# Sheet1.net
KiCad netlist of a schematic drawn in Altium Designer
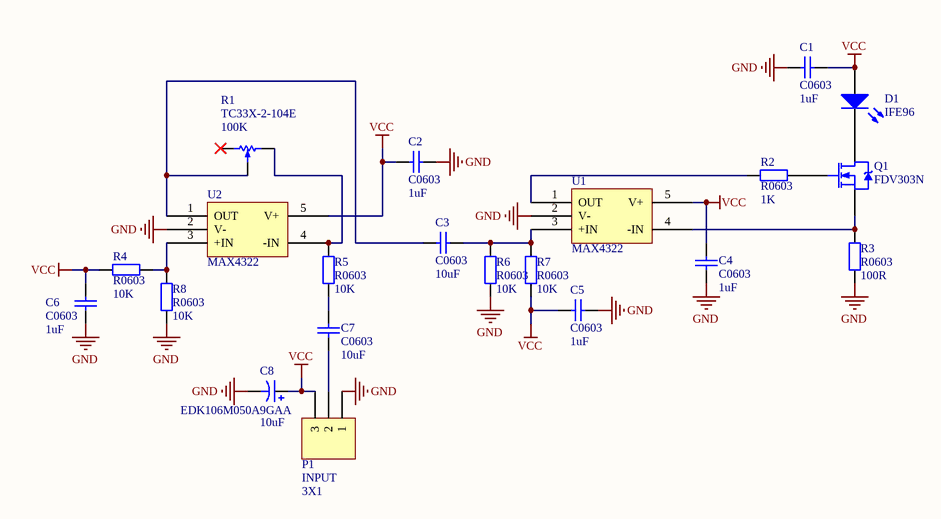
[diagram p0: Sheet1.SchDoc]

(export (version "E")
  (design (tool "Eeschema 10.0.6"))
  (components
    (comp (ref "C1")
      (value "C0603")
      (footprint "1608[0603]")
      (description "Ceramic Capacitor")
      (fields (field (name "ALTIUM_VALUE") "1uF"))
      (libsource (lib "Miscellaneous Devices Local Copy") (part "Cap"))
    )
    (comp (ref "C2")
      (value "C0603")
      (footprint "1608[0603]")
      (description "Ceramic Capacitor")
      (fields (field (name "ALTIUM_VALUE") "1uF"))
      (libsource (lib "Miscellaneous Devices Local Copy") (part "Cap"))
    )
    (comp (ref "C3")
      (value "C0603")
      (footprint "1608[0603]")
      (description "Ceramic Capacitor")
      (fields (field (name "ALTIUM_VALUE") "10uF"))
      (libsource (lib "Miscellaneous Devices Local Copy") (part "Cap"))
    )
    (comp (ref "C4")
      (value "C0603")
      (footprint "1608[0603]")
      (description "Ceramic Capacitor")
      (fields (field (name "ALTIUM_VALUE") "1uF"))
      (libsource (lib "Miscellaneous Devices Local Copy") (part "Cap"))
    )
    (comp (ref "C5")
      (value "C0603")
      (footprint "1608[0603]")
      (description "Ceramic Capacitor")
      (fields (field (name "ALTIUM_VALUE") "1uF"))
      (libsource (lib "Miscellaneous Devices Local Copy") (part "Cap"))
    )
    (comp (ref "C6")
      (value "C0603")
      (footprint "1608[0603]")
      (description "Ceramic Capacitor")
      (fields (field (name "ALTIUM_VALUE") "1uF"))
      (libsource (lib "Miscellaneous Devices Local Copy") (part "Cap"))
    )
    (comp (ref "C7")
      (value "C0603")
      (footprint "1608[0603]")
      (description "Ceramic Capacitor")
      (fields (field (name "ALTIUM_VALUE") "10uF"))
      (libsource (lib "Miscellaneous Devices Local Copy") (part "Cap"))
    )
    (comp (ref "C8")
      (value "EDK106M050A9GAA")
      (footprint "EDK106M050A9GAA")
      (description "Aluminium Electrolytic Capacitor")
      (fields (field (name "ALTIUM_VALUE") "10uF"))
      (libsource (lib "Miscellaneous Devices Local Copy") (part "Cap Pol1"))
    )
    (comp (ref "D1")
      (value "IFE96")
      (footprint "IFE96")
      (description "Red LED For PMMA")
      (libsource (lib "Schlib1") (part "IFE96"))
    )
    (comp (ref "P1")
      (value "INPUT")
      (footprint "HDR1X3")
      (description "Header, 3-Pin")
      (fields (field (name "ALTIUM_VALUE") "3X1"))
      (libsource (lib "Miscellaneous Connectors Local Copy") (part "Header 3"))
    )
    (comp (ref "Q1")
      (value "FDV303N")
      (footprint "SOT23_M")
      (description "N-channel MOS FET Transistor")
      (libsource (lib "Schlib1") (part "FDV303N"))
    )
    (comp (ref "R1")
      (value "TC33X-2-104E")
      (footprint "TC33X-2-104E")
      (description "Potentiometer")
      (fields (field (name "ALTIUM_VALUE") "100K"))
      (libsource (lib "Schlib1") (part "TC33X-2-104E"))
    )
    (comp (ref "R2")
      (value "R0603")
      (footprint "J1-0603")
      (description "Resistor")
      (fields (field (name "ALTIUM_VALUE") "1K"))
      (libsource (lib "Miscellaneous Devices Local Copy") (part "Res2"))
    )
    (comp (ref "R3")
      (value "R0603")
      (footprint "J1-0603")
      (description "Resistor")
      (fields (field (name "ALTIUM_VALUE") "100R"))
      (libsource (lib "") (part "Res2_1"))
    )
    (comp (ref "R4")
      (value "R0603")
      (footprint "J1-0603")
      (description "Resistor")
      (fields (field (name "ALTIUM_VALUE") "10K"))
      (libsource (lib "Miscellaneous Devices Local Copy") (part "Res2"))
    )
    (comp (ref "R5")
      (value "R0603")
      (footprint "J1-0603")
      (description "Resistor")
      (fields (field (name "ALTIUM_VALUE") "10K"))
      (libsource (lib "") (part "Res2_1"))
    )
    (comp (ref "R6")
      (value "R0603")
      (footprint "J1-0603")
      (description "Resistor")
      (fields (field (name "ALTIUM_VALUE") "10K"))
      (libsource (lib "") (part "Res2_1"))
    )
    (comp (ref "R7")
      (value "R0603")
      (footprint "J1-0603")
      (description "Resistor")
      (fields (field (name "ALTIUM_VALUE") "10K"))
      (libsource (lib "") (part "Res2_1"))
    )
    (comp (ref "R8")
      (value "R0603")
      (footprint "J1-0603")
      (description "Resistor")
      (fields (field (name "ALTIUM_VALUE") "10K"))
      (libsource (lib "") (part "Res2_2"))
    )
    (comp (ref "U1")
      (value "MAX4322")
      (footprint "MAX4322_SOT23-5")
      (description "Single Supply Operational Amplifier")
      (libsource (lib "Schlib1") (part "MAX4322"))
    )
    (comp (ref "U2")
      (value "MAX4322")
      (footprint "MAX4322_SOT23-5")
      (description "Single Supply Operational Amplifier")
      (libsource (lib "Schlib1") (part "MAX4322"))
    )
  )
  (nets
    (net (code "1") (name "GND") (class "Default")
      (node (ref "C1") (pin "2") (pinfunction "2_2") (pintype "passive"))
      (node (ref "C2") (pin "2") (pinfunction "2_2") (pintype "passive"))
      (node (ref "C4") (pin "1") (pinfunction "1_1") (pintype "passive"))
      (node (ref "C5") (pin "2") (pinfunction "2_2") (pintype "passive"))
      (node (ref "C6") (pin "1") (pinfunction "1_1") (pintype "passive"))
      (node (ref "C8") (pin "2") (pinfunction "2_2") (pintype "passive"))
      (node (ref "P1") (pin "1") (pinfunction "1_1") (pintype "passive"))
      (node (ref "R3") (pin "2") (pinfunction "2_2") (pintype "passive"))
      (node (ref "R6") (pin "2") (pinfunction "2_2") (pintype "passive"))
      (node (ref "R8") (pin "1") (pinfunction "1_1") (pintype "passive"))
      (node (ref "U1") (pin "2") (pinfunction "V-_2") (pintype "passive"))
      (node (ref "U2") (pin "2") (pinfunction "V-_2") (pintype "passive"))
    )
    (net (code "2") (name "Net-(C7-Pad1)") (class "Default")
      (node (ref "C7") (pin "1") (pinfunction "1_1") (pintype "passive"))
      (node (ref "P1") (pin "2") (pinfunction "2_2") (pintype "passive"))
    )
    (net (code "3") (name "Net-(C7-Pad2)") (class "Default")
      (node (ref "C7") (pin "2") (pinfunction "2_2") (pintype "passive"))
      (node (ref "R5") (pin "2") (pinfunction "2_2") (pintype "passive"))
    )
    (net (code "4") (name "Net-(D1-K)") (class "Default")
      (node (ref "D1") (pin "1") (pinfunction "K_1") (pintype "passive"))
      (node (ref "Q1") (pin "2") (pinfunction "D_2") (pintype "passive"))
    )
    (net (code "5") (name "Net-(Q1-G)") (class "Default")
      (node (ref "Q1") (pin "1") (pinfunction "G_1") (pintype "passive"))
      (node (ref "R2") (pin "2") (pinfunction "2_2") (pintype "passive"))
    )
    (net (code "6") (name "Net-(Q1-S)") (class "Default")
      (node (ref "Q1") (pin "3") (pinfunction "S_3") (pintype "passive"))
      (node (ref "R3") (pin "1") (pinfunction "1_1") (pintype "passive"))
      (node (ref "U1") (pin "4") (pinfunction "-IN_4") (pintype "passive"))
    )
    (net (code "7") (name "Net-(R1-+)") (class "Default")
      (node (ref "R1") (pin "1") (pinfunction "+_1") (pintype "passive"))
      (node (ref "R5") (pin "1") (pinfunction "1_1") (pintype "passive"))
      (node (ref "U2") (pin "4") (pinfunction "-IN_4") (pintype "passive"))
    )
    (net (code "8") (name "Net-(R1-W)") (class "Default")
      (node (ref "C3") (pin "2") (pinfunction "2_2") (pintype "passive"))
      (node (ref "R1") (pin "2") (pinfunction "W_2") (pintype "passive"))
      (node (ref "U2") (pin "1") (pinfunction "OUT_1") (pintype "passive"))
    )
    (net (code "9") (name "Net-(U1-+IN)") (class "Default")
      (node (ref "C3") (pin "1") (pinfunction "1_1") (pintype "passive"))
      (node (ref "R6") (pin "1") (pinfunction "1_1") (pintype "passive"))
      (node (ref "R7") (pin "1") (pinfunction "1_1") (pintype "passive"))
      (node (ref "U1") (pin "3") (pinfunction "+IN_3") (pintype "passive"))
    )
    (net (code "10") (name "Net-(U1-OUT)") (class "Default")
      (node (ref "R2") (pin "1") (pinfunction "1_1") (pintype "passive"))
      (node (ref "U1") (pin "1") (pinfunction "OUT_1") (pintype "passive"))
    )
    (net (code "11") (name "Net-(U2-+IN)") (class "Default")
      (node (ref "R4") (pin "2") (pinfunction "2_2") (pintype "passive"))
      (node (ref "R8") (pin "2") (pinfunction "2_2") (pintype "passive"))
      (node (ref "U2") (pin "3") (pinfunction "+IN_3") (pintype "passive"))
    )
    (net (code "12") (name "VCC") (class "Default")
      (node (ref "C1") (pin "1") (pinfunction "1_1") (pintype "passive"))
      (node (ref "C2") (pin "1") (pinfunction "1_1") (pintype "passive"))
      (node (ref "C4") (pin "2") (pinfunction "2_2") (pintype "passive"))
      (node (ref "C5") (pin "1") (pinfunction "1_1") (pintype "passive"))
      (node (ref "C6") (pin "2") (pinfunction "2_2") (pintype "passive"))
      (node (ref "C8") (pin "1") (pinfunction "1_1") (pintype "passive"))
      (node (ref "D1") (pin "2") (pinfunction "A_2") (pintype "passive"))
      (node (ref "P1") (pin "3") (pinfunction "3_3") (pintype "passive"))
      (node (ref "R4") (pin "1") (pinfunction "1_1") (pintype "passive"))
      (node (ref "R7") (pin "2") (pinfunction "2_2") (pintype "passive"))
      (node (ref "U1") (pin "5") (pinfunction "V+_5") (pintype "passive"))
      (node (ref "U2") (pin "5") (pinfunction "V+_5") (pintype "passive"))
    )
    (net (code "13") (name "unconnected-(R1---Pad3)") (class "Default")
      (node (ref "R1") (pin "3") (pinfunction "-_3") (pintype "passive+no_connect"))
    )
  )
)
